# Preliminary_Schematic.net
KiCad netlist of a schematic drawn in EAGLE
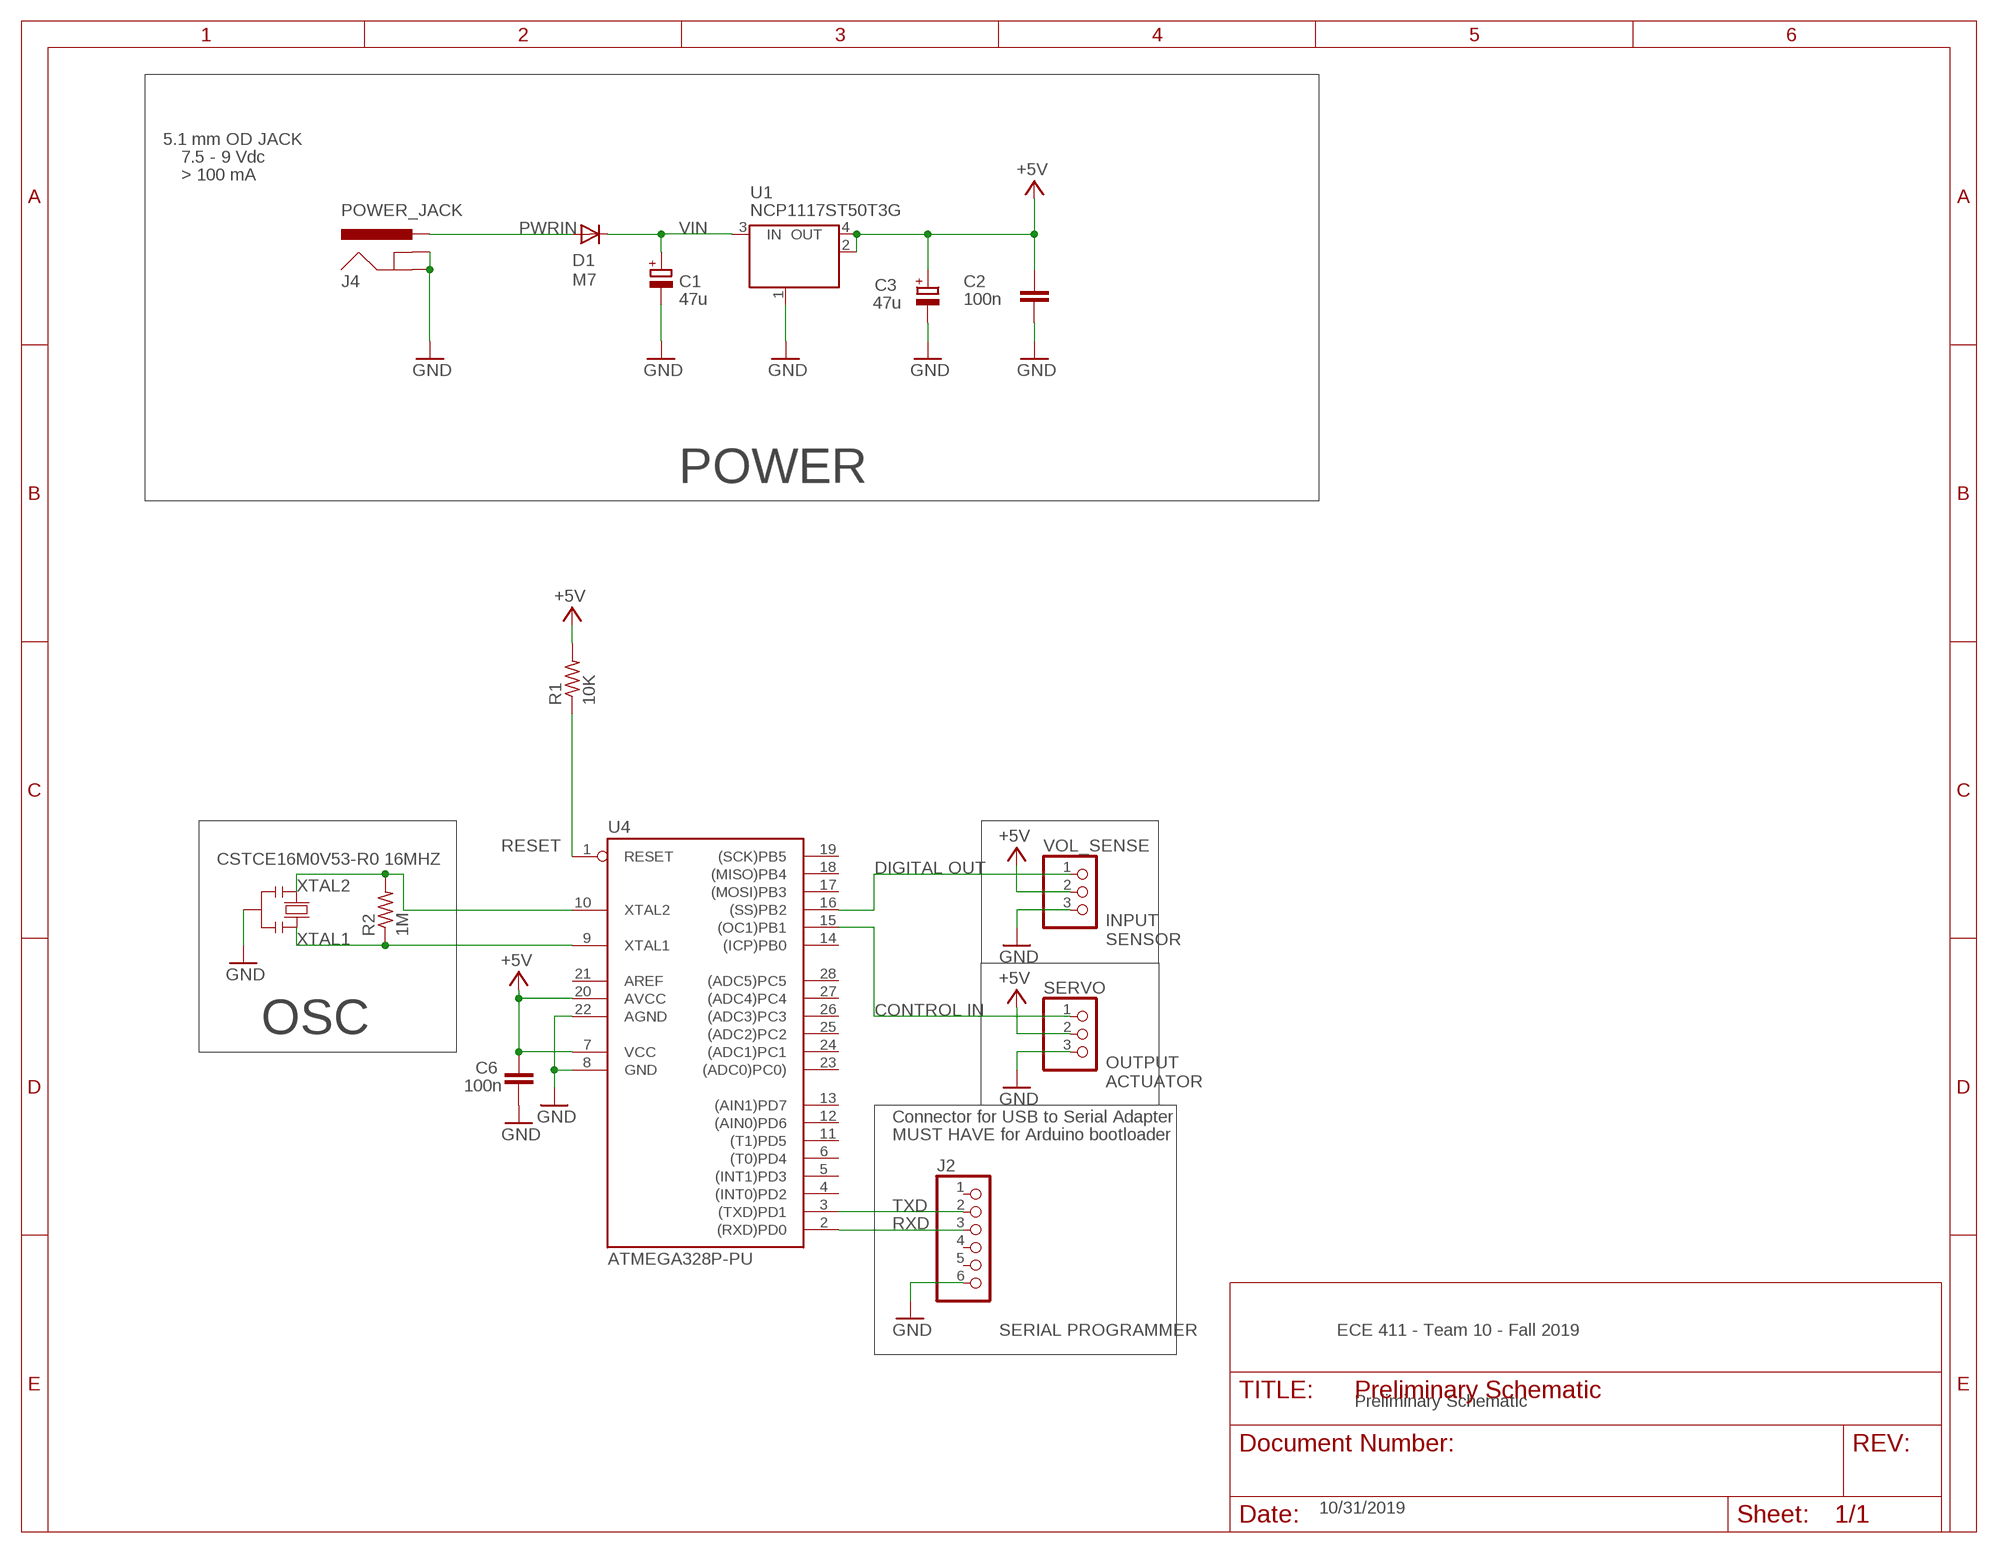
[diagram p0: schematic, sheet 1]

(export (version "E")
  (design (tool "Eeschema 10.0.6"))
  (components
    (comp (ref "C1")
      (value "47u")
      (footprint "eagle-import:PANASONIC_D")
      (libsource (lib "eagle-import") (part "CPOL-EUD"))
    )
    (comp (ref "C2")
      (value "100n")
      (footprint "eagle-import:C0805")
      (libsource (lib "eagle-import") (part "C-EUC0805"))
    )
    (comp (ref "C3")
      (value "47u")
      (footprint "eagle-import:PANASONIC_D")
      (libsource (lib "eagle-import") (part "CPOL-EUD"))
    )
    (comp (ref "C6")
      (value "100n")
      (footprint "eagle-import:C0805")
      (libsource (lib "eagle-import") (part "C-EUC0805"))
    )
    (comp (ref "D1")
      (value "M7")
      (footprint "eagle-import:SMB")
      (libsource (lib "eagle-import") (part "DIODE-SMB"))
    )
    (comp (ref "J2")
      (value "PINHD-1X6")
      (footprint "eagle-import:1X06")
      (libsource (lib "eagle-import") (part "PINHD-1X6"))
    )
    (comp (ref "J4")
      (value "POWER_JACK")
      (footprint "eagle-import:POWER_JACK_PTH")
      (libsource (lib "eagle-import") (part "POWER_JACK"))
    )
    (comp (ref "R1")
      (value "10K")
      (footprint "eagle-import:R0805")
      (libsource (lib "eagle-import") (part "R-US_R0805"))
    )
    (comp (ref "R2")
      (value "1M")
      (footprint "eagle-import:R0805")
      (libsource (lib "eagle-import") (part "R-US_R0805"))
    )
    (comp (ref "SERVO")
      (value "PINHD-1X3")
      (footprint "eagle-import:1X03")
      (libsource (lib "eagle-import") (part "PINHD-1X3"))
    )
    (comp (ref "U1")
      (value "NCP1117ST50T3G")
      (footprint "eagle-import:SOT223")
      (libsource (lib "eagle-import") (part "MC33269ST-3.3T3"))
    )
    (comp (ref "U4")
      (value "ATMEGA328P-PU")
      (footprint "eagle-import:DIL28-3")
      (libsource (lib "eagle-import") (part "ATMEGA328P-PU"))
    )
    (comp (ref "VOL_SENSE")
      (value "PINHD-1X3")
      (footprint "eagle-import:1X03")
      (libsource (lib "eagle-import") (part "PINHD-1X3"))
    )
    (comp (ref "X1")
      (value "CSTCE16M0V53-R0 16MHZ")
      (footprint "eagle-import:RESONATOR")
      (libsource (lib "eagle-import") (part "RESONATORMU"))
    )
  )
  (nets
    (net (code "1") (name "+5V") (class "Default")
      (node (ref "C2") (pin "2") (pinfunction "2_2") (pintype "passive"))
      (node (ref "C3") (pin "+") (pinfunction "+_+") (pintype "passive"))
      (node (ref "C6") (pin "2") (pinfunction "2_2") (pintype "passive"))
      (node (ref "R1") (pin "2") (pinfunction "2_2") (pintype "passive"))
      (node (ref "SERVO") (pin "2") (pinfunction "2_2") (pintype "passive"))
      (node (ref "U1") (pin "2") (pinfunction "OUT_2") (pintype "passive"))
      (node (ref "U1") (pin "4") (pinfunction "OUT_4") (pintype "passive"))
      (node (ref "U4") (pin "20") (pinfunction "AVCC_20") (pintype "power_in"))
      (node (ref "U4") (pin "7") (pinfunction "VCC_7") (pintype "power_in"))
      (node (ref "VOL_SENSE") (pin "2") (pinfunction "2_2") (pintype "passive"))
    )
    (net (code "2") (name "/PWRIN") (class "Default")
      (node (ref "D1") (pin "A") (pinfunction "A_A") (pintype "passive"))
      (node (ref "J4") (pin "PWR") (pinfunction "PWR_PWR") (pintype "bidirectional"))
    )
    (net (code "3") (name "/RESET") (class "Default")
      (node (ref "R1") (pin "1") (pinfunction "1_1") (pintype "passive"))
      (node (ref "U4") (pin "1") (pinfunction "RESET_1") (pintype "input"))
    )
    (net (code "4") (name "/RXD") (class "Default")
      (node (ref "J2") (pin "3") (pinfunction "3_3") (pintype "passive"))
      (node (ref "U4") (pin "2") (pinfunction "(RXD)PD0_2") (pintype "bidirectional"))
    )
    (net (code "5") (name "/TXD") (class "Default")
      (node (ref "J2") (pin "2") (pinfunction "2_2") (pintype "passive"))
      (node (ref "U4") (pin "3") (pinfunction "(TXD)PD1_3") (pintype "bidirectional"))
    )
    (net (code "6") (name "/VIN") (class "Default")
      (node (ref "C1") (pin "+") (pinfunction "+_+") (pintype "passive"))
      (node (ref "D1") (pin "C") (pinfunction "C_C") (pintype "passive"))
      (node (ref "U1") (pin "3") (pinfunction "IN_3") (pintype "input"))
    )
    (net (code "7") (name "/XTAL1") (class "Default")
      (node (ref "R2") (pin "1") (pinfunction "1_1") (pintype "passive"))
      (node (ref "U4") (pin "9") (pinfunction "XTAL1_9") (pintype "bidirectional"))
      (node (ref "X1") (pin "3") (pinfunction "3_3") (pintype "passive"))
    )
    (net (code "8") (name "/XTAL2") (class "Default")
      (node (ref "R2") (pin "2") (pinfunction "2_2") (pintype "passive"))
      (node (ref "U4") (pin "10") (pinfunction "XTAL2_10") (pintype "bidirectional"))
      (node (ref "X1") (pin "1") (pinfunction "1_1") (pintype "passive"))
    )
    (net (code "9") (name "GND") (class "Default")
      (node (ref "C1") (pin "-") (pinfunction "-_-") (pintype "passive"))
      (node (ref "C2") (pin "1") (pinfunction "1_1") (pintype "passive"))
      (node (ref "C3") (pin "-") (pinfunction "-_-") (pintype "passive"))
      (node (ref "C6") (pin "1") (pinfunction "1_1") (pintype "passive"))
      (node (ref "J2") (pin "6") (pinfunction "6_6") (pintype "passive"))
      (node (ref "J4") (pin "GND") (pinfunction "GND_GND") (pintype "bidirectional"))
      (node (ref "J4") (pin "GNDBREAK") (pinfunction "GNDBREAK_GNDBREAK") (pintype "bidirectional"))
      (node (ref "SERVO") (pin "3") (pinfunction "3_3") (pintype "passive"))
      (node (ref "U1") (pin "1") (pinfunction "GND/ADJ_1") (pintype "input"))
      (node (ref "U4") (pin "22") (pinfunction "AGND_22") (pintype "power_in"))
      (node (ref "U4") (pin "8") (pinfunction "GND_8") (pintype "power_in"))
      (node (ref "VOL_SENSE") (pin "3") (pinfunction "3_3") (pintype "passive"))
      (node (ref "X1") (pin "2") (pinfunction "2_2") (pintype "passive"))
    )
    (net (code "10") (name "Net-(U4-(OC1)PB1)") (class "Default")
      (node (ref "SERVO") (pin "1") (pinfunction "1_1") (pintype "passive"))
      (node (ref "U4") (pin "15") (pinfunction "(OC1)PB1_15") (pintype "bidirectional"))
    )
    (net (code "11") (name "Net-(U4-(SS)PB2)") (class "Default")
      (node (ref "U4") (pin "16") (pinfunction "(SS)PB2_16") (pintype "bidirectional"))
      (node (ref "VOL_SENSE") (pin "1") (pinfunction "1_1") (pintype "passive"))
    )
    (net (code "12") (name "unconnected-(J2-Pad1)") (class "Default")
      (node (ref "J2") (pin "1") (pinfunction "1_1") (pintype "passive"))
    )
    (net (code "13") (name "unconnected-(J2-Pad4)") (class "Default")
      (node (ref "J2") (pin "4") (pinfunction "4_4") (pintype "passive"))
    )
    (net (code "14") (name "unconnected-(J2-Pad5)") (class "Default")
      (node (ref "J2") (pin "5") (pinfunction "5_5") (pintype "passive"))
    )
    (net (code "15") (name "unconnected-(U4-(ADC0)PC0)-Pad23)") (class "Default")
      (node (ref "U4") (pin "23") (pinfunction "(ADC0)PC0)_23") (pintype "bidirectional"))
    )
    (net (code "16") (name "unconnected-(U4-(ADC1)PC1-Pad24)") (class "Default")
      (node (ref "U4") (pin "24") (pinfunction "(ADC1)PC1_24") (pintype "bidirectional"))
    )
    (net (code "17") (name "unconnected-(U4-(ADC2)PC2-Pad25)") (class "Default")
      (node (ref "U4") (pin "25") (pinfunction "(ADC2)PC2_25") (pintype "bidirectional"))
    )
    (net (code "18") (name "unconnected-(U4-(ADC3)PC3-Pad26)") (class "Default")
      (node (ref "U4") (pin "26") (pinfunction "(ADC3)PC3_26") (pintype "bidirectional"))
    )
    (net (code "19") (name "unconnected-(U4-(ADC4)PC4-Pad27)") (class "Default")
      (node (ref "U4") (pin "27") (pinfunction "(ADC4)PC4_27") (pintype "bidirectional"))
    )
    (net (code "20") (name "unconnected-(U4-(ADC5)PC5-Pad28)") (class "Default")
      (node (ref "U4") (pin "28") (pinfunction "(ADC5)PC5_28") (pintype "bidirectional"))
    )
    (net (code "21") (name "unconnected-(U4-(AIN0)PD6-Pad12)") (class "Default")
      (node (ref "U4") (pin "12") (pinfunction "(AIN0)PD6_12") (pintype "bidirectional"))
    )
    (net (code "22") (name "unconnected-(U4-(AIN1)PD7-Pad13)") (class "Default")
      (node (ref "U4") (pin "13") (pinfunction "(AIN1)PD7_13") (pintype "bidirectional"))
    )
    (net (code "23") (name "unconnected-(U4-(ICP)PB0-Pad14)") (class "Default")
      (node (ref "U4") (pin "14") (pinfunction "(ICP)PB0_14") (pintype "bidirectional"))
    )
    (net (code "24") (name "unconnected-(U4-(INT0)PD2-Pad4)") (class "Default")
      (node (ref "U4") (pin "4") (pinfunction "(INT0)PD2_4") (pintype "bidirectional"))
    )
    (net (code "25") (name "unconnected-(U4-(INT1)PD3-Pad5)") (class "Default")
      (node (ref "U4") (pin "5") (pinfunction "(INT1)PD3_5") (pintype "bidirectional"))
    )
    (net (code "26") (name "unconnected-(U4-(MISO)PB4-Pad18)") (class "Default")
      (node (ref "U4") (pin "18") (pinfunction "(MISO)PB4_18") (pintype "bidirectional"))
    )
    (net (code "27") (name "unconnected-(U4-(MOSI)PB3-Pad17)") (class "Default")
      (node (ref "U4") (pin "17") (pinfunction "(MOSI)PB3_17") (pintype "bidirectional"))
    )
    (net (code "28") (name "unconnected-(U4-(SCK)PB5-Pad19)") (class "Default")
      (node (ref "U4") (pin "19") (pinfunction "(SCK)PB5_19") (pintype "bidirectional"))
    )
    (net (code "29") (name "unconnected-(U4-(T0)PD4-Pad6)") (class "Default")
      (node (ref "U4") (pin "6") (pinfunction "(T0)PD4_6") (pintype "bidirectional"))
    )
    (net (code "30") (name "unconnected-(U4-(T1)PD5-Pad11)") (class "Default")
      (node (ref "U4") (pin "11") (pinfunction "(T1)PD5_11") (pintype "bidirectional"))
    )
    (net (code "31") (name "unconnected-(U4-AREF-Pad21)") (class "Default")
      (node (ref "U4") (pin "21") (pinfunction "AREF_21") (pintype "passive"))
    )
  )
)
